# untitled.net
KiCad netlist of a schematic drawn in EAGLE
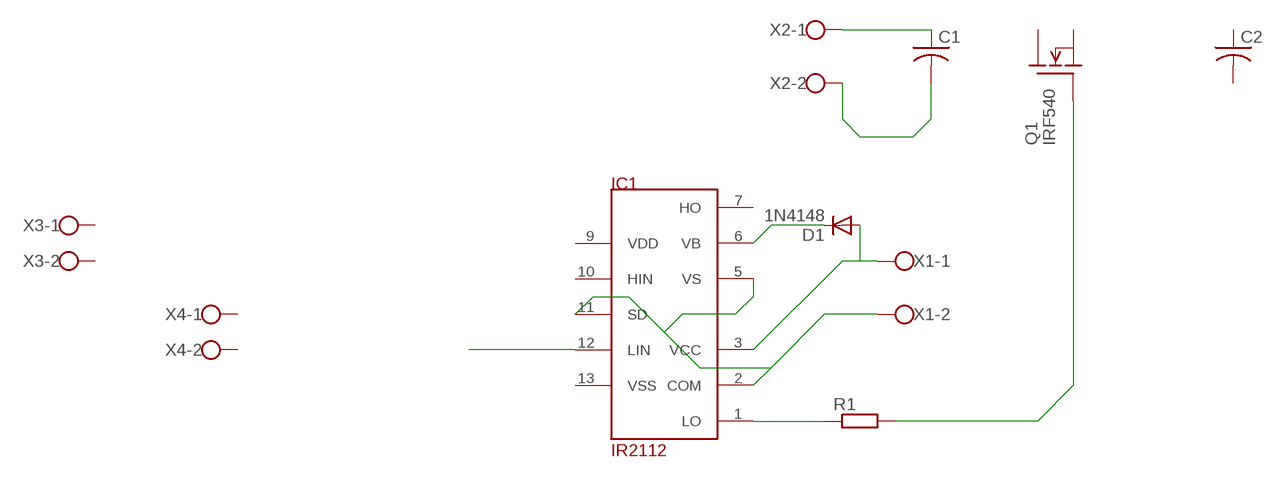
[diagram p0: schematic, sheet 1]

(export (version "E")
  (design (tool "Eeschema 10.0.6"))
  (components
    (comp (ref "C1")
      (value "C-US050-045X075")
      (footprint "eagle-import:C050-045X075")
      (libsource (lib "eagle-import") (part "C-US050-045X075"))
    )
    (comp (ref "C2")
      (value "C-US050-045X075")
      (footprint "eagle-import:C050-045X075")
      (libsource (lib "eagle-import") (part "C-US050-045X075"))
    )
    (comp (ref "D1")
      (value "1N4148")
      (footprint "eagle-import:DO35-10")
      (libsource (lib "eagle-import") (part "1N4148"))
    )
    (comp (ref "IC1")
      (value "IR2112")
      (footprint "eagle-import:DIL14")
      (libsource (lib "eagle-import") (part "IR2112"))
    )
    (comp (ref "Q1")
      (value "IRF540")
      (footprint "eagle-import:TO220")
      (libsource (lib "eagle-import") (part "IRF540"))
    )
    (comp (ref "R1")
      (value "R-EU_0207/10")
      (footprint "eagle-import:0207_10")
      (libsource (lib "eagle-import") (part "R-EU_0207/10"))
    )
    (comp (ref "X1")
      (value "AK300/2")
      (footprint "eagle-import:AK300_2")
      (libsource (lib "eagle-import") (part "AK300/2"))
    )
    (comp (ref "X2")
      (value "AK300/2")
      (footprint "eagle-import:AK300_2")
      (libsource (lib "eagle-import") (part "AK300/2"))
    )
    (comp (ref "X3")
      (value "AK300/2")
      (footprint "eagle-import:AK300_2")
      (libsource (lib "eagle-import") (part "AK300/2"))
    )
    (comp (ref "X4")
      (value "AK300/2")
      (footprint "eagle-import:AK300_2")
      (libsource (lib "eagle-import") (part "AK300/2"))
    )
  )
  (nets
    (net (code "1") (name "/VDD") (class "Default")
      (node (ref "IC1") (pin "9") (pinfunction "VDD_9") (pintype "power_in"))
    )
    (net (code "2") (name "/VSS") (class "Default")
      (node (ref "IC1") (pin "13") (pinfunction "VSS_13") (pintype "power_in"))
    )
    (net (code "3") (name "Net-(IC1-COM)") (class "Default")
      (node (ref "IC1") (pin "11") (pinfunction "SD_11") (pintype "input"))
      (node (ref "IC1") (pin "2") (pinfunction "COM_2") (pintype "power_in"))
      (node (ref "IC1") (pin "5") (pinfunction "VS_5") (pintype "power_in"))
      (node (ref "X1") (pin "2") (pinfunction "KL_2") (pintype "passive"))
    )
    (net (code "4") (name "Net-(IC1-LO)") (class "Default")
      (node (ref "IC1") (pin "1") (pinfunction "LO_1") (pintype "output"))
      (node (ref "R1") (pin "1") (pinfunction "1_1") (pintype "passive"))
    )
    (net (code "5") (name "Net-(IC1-VB)") (class "Default")
      (node (ref "D1") (pin "C") (pinfunction "C_C") (pintype "passive"))
      (node (ref "IC1") (pin "6") (pinfunction "VB_6") (pintype "power_in"))
    )
    (net (code "6") (name "Net-(IC1-VCC)") (class "Default")
      (node (ref "D1") (pin "A") (pinfunction "A_A") (pintype "passive"))
      (node (ref "IC1") (pin "3") (pinfunction "VCC_3") (pintype "power_in"))
      (node (ref "X1") (pin "1") (pinfunction "KL_1") (pintype "passive"))
    )
    (net (code "7") (name "Net-(Q1-G)") (class "Default")
      (node (ref "Q1") (pin "1") (pinfunction "G_1") (pintype "passive"))
      (node (ref "R1") (pin "2") (pinfunction "2_2") (pintype "passive"))
    )
    (net (code "8") (name "Net-(X2A-KL)") (class "Default")
      (node (ref "C1") (pin "1") (pinfunction "1_1") (pintype "passive"))
      (node (ref "X2") (pin "1") (pinfunction "KL_1") (pintype "passive"))
    )
    (net (code "9") (name "Net-(X2B-KL)") (class "Default")
      (node (ref "C1") (pin "2") (pinfunction "2_2") (pintype "passive"))
      (node (ref "X2") (pin "2") (pinfunction "KL_2") (pintype "passive"))
    )
    (net (code "10") (name "unconnected-(C2-Pad1)") (class "Default")
      (node (ref "C2") (pin "1") (pinfunction "1_1") (pintype "passive"))
    )
    (net (code "11") (name "unconnected-(C2-Pad2)") (class "Default")
      (node (ref "C2") (pin "2") (pinfunction "2_2") (pintype "passive"))
    )
    (net (code "12") (name "unconnected-(IC1-HIN-Pad10)") (class "Default")
      (node (ref "IC1") (pin "10") (pinfunction "HIN_10") (pintype "input"))
    )
    (net (code "13") (name "unconnected-(IC1-HO-Pad7)") (class "Default")
      (node (ref "IC1") (pin "7") (pinfunction "HO_7") (pintype "output"))
    )
    (net (code "14") (name "unconnected-(IC1-LIN-Pad12)") (class "Default")
      (node (ref "IC1") (pin "12") (pinfunction "LIN_12") (pintype "input"))
    )
    (net (code "15") (name "unconnected-(Q1-D-Pad2)") (class "Default")
      (node (ref "Q1") (pin "2") (pinfunction "D_2") (pintype "passive"))
    )
    (net (code "16") (name "unconnected-(Q1-S-Pad3)") (class "Default")
      (node (ref "Q1") (pin "3") (pinfunction "S_3") (pintype "passive"))
    )
    (net (code "17") (name "unconnected-(X3A-KL-Pad1)") (class "Default")
      (node (ref "X3") (pin "1") (pinfunction "KL_1") (pintype "passive"))
    )
    (net (code "18") (name "unconnected-(X3B-KL-Pad2)") (class "Default")
      (node (ref "X3") (pin "2") (pinfunction "KL_2") (pintype "passive"))
    )
    (net (code "19") (name "unconnected-(X4A-KL-Pad1)") (class "Default")
      (node (ref "X4") (pin "1") (pinfunction "KL_1") (pintype "passive"))
    )
    (net (code "20") (name "unconnected-(X4B-KL-Pad2)") (class "Default")
      (node (ref "X4") (pin "2") (pinfunction "KL_2") (pintype "passive"))
    )
  )
)
